# alu_schem_1.net
KiCad netlist of a schematic drawn in Altium Designer
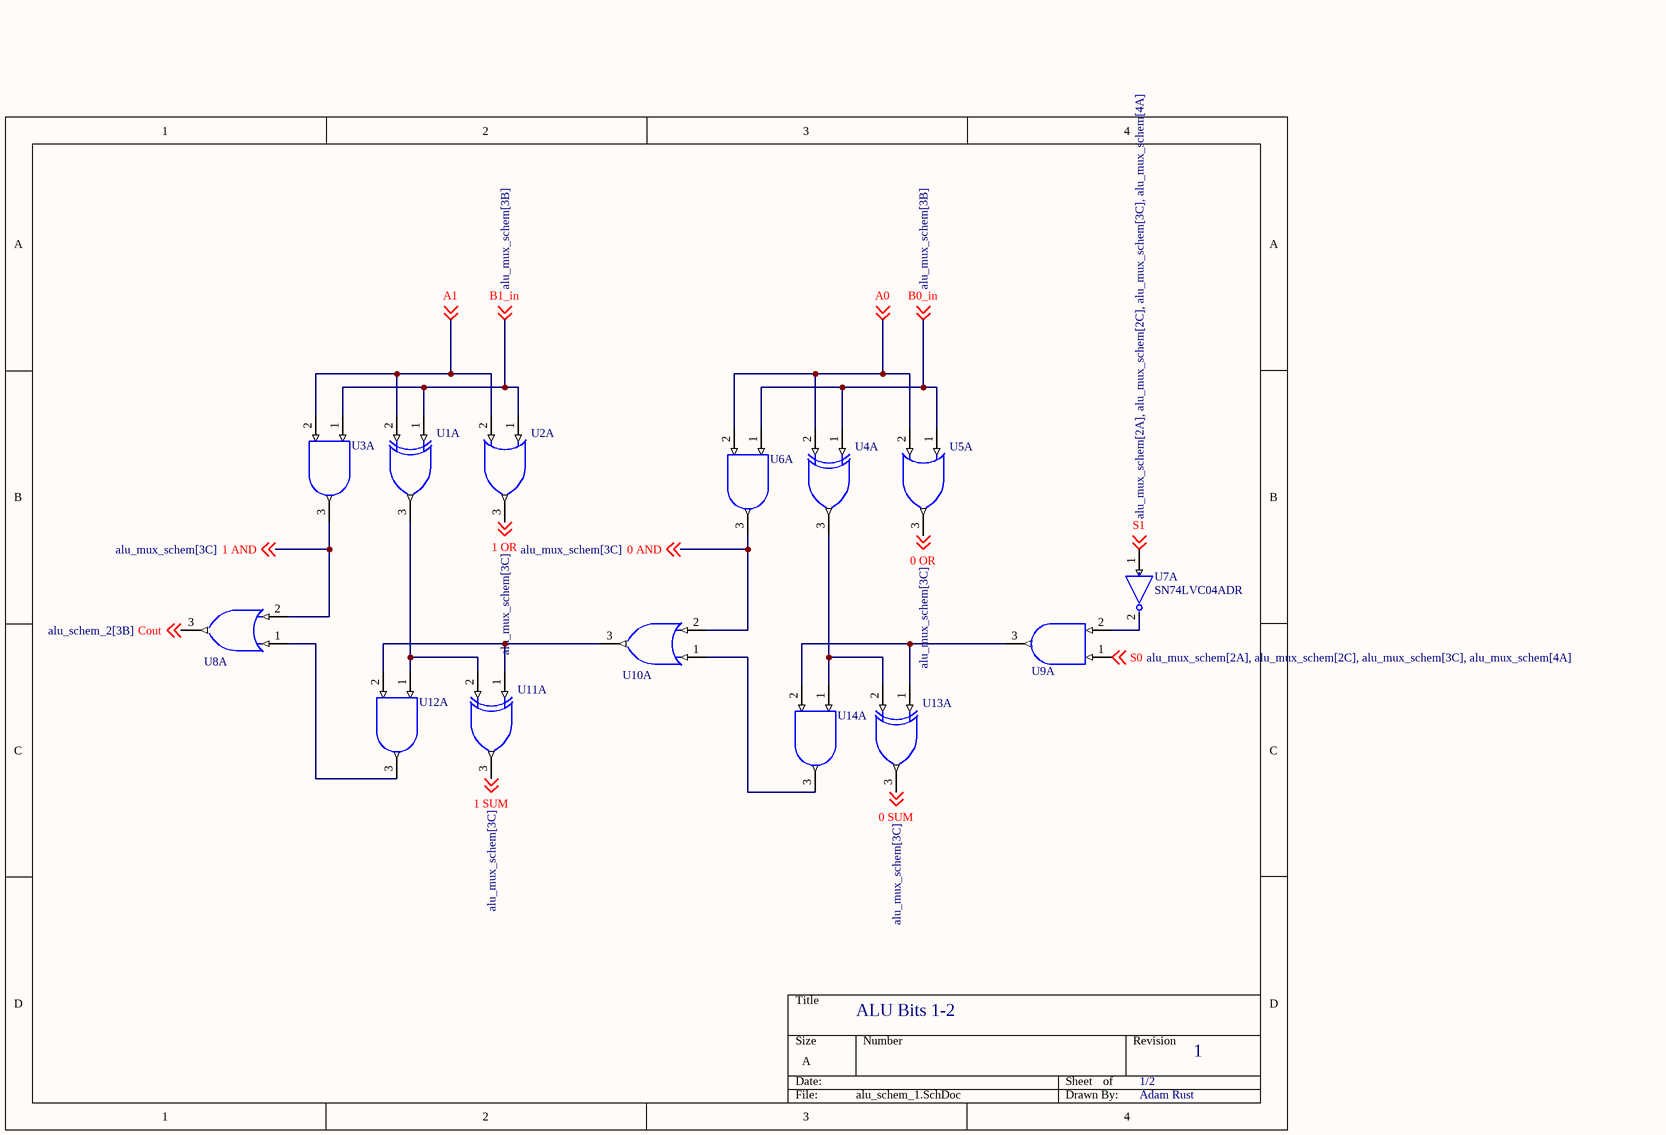
[diagram p0: alu_schem_1.SchDoc]

(export (version "E")
  (design (tool "Eeschema 10.0.6"))
  (components
    (comp (ref "U1")
      (value "SN74LVC86ARGYR")
      (footprint "RGY0014A_V")
      (description "Quadruple 2-Input Exclusive-OR Gate, RGY0014A, LARGE T&R")
      (fields
        (field (name "GENERIC PART NUMBER") "SN74LVC86A")
        (field (name "MANUFACTURER") "Texas Instruments")
      )
      (libsource (lib "Altium Content Vault") (part "TI-XOR-4-2IN-RGY0014A-14"))
    )
    (comp (ref "U2")
      (value "SN74LVC32APWRG4")
      (footprint "PW0014A_N")
      (description "Quadruple 2-Input Positive-OR Gate, PW0014A, LARGE T&R")
      (fields
        (field (name "GENERIC PART NUMBER") "SN74LVC32A")
        (field (name "MANUFACTURER") "Texas Instruments")
      )
      (libsource (lib "Altium Content Vault") (part "TI-OR-4-2IN-14"))
    )
    (comp (ref "U3")
      (value "SN74LVC08ADR")
      (footprint "D0014A_N")
      (description "Quadruple 2-Input Positive-AND Gate, D0014A, LARGE T&R")
      (fields
        (field (name "MANUFACTURER") "Texas Instruments")
        (field (name "GENERIC PART NUMBER") "SN74LVC08A")
      )
      (libsource (lib "Altium Content Vault") (part "TI-AND-4-2IN-14"))
    )
    (comp (ref "U4")
      (value "SN74LVC86ARGYR")
      (footprint "RGY0014A_V")
      (description "Quadruple 2-Input Exclusive-OR Gate, RGY0014A, LARGE T&R")
      (fields
        (field (name "GENERIC PART NUMBER") "SN74LVC86A")
        (field (name "MANUFACTURER") "Texas Instruments")
      )
      (libsource (lib "Altium Content Vault") (part "TI-XOR-4-2IN-RGY0014A-14"))
    )
    (comp (ref "U5")
      (value "SN74LVC32APWRG4")
      (footprint "PW0014A_N")
      (description "Quadruple 2-Input Positive-OR Gate, PW0014A, LARGE T&R")
      (fields
        (field (name "GENERIC PART NUMBER") "SN74LVC32A")
        (field (name "MANUFACTURER") "Texas Instruments")
      )
      (libsource (lib "Altium Content Vault") (part "TI-OR-4-2IN-14"))
    )
    (comp (ref "U6")
      (value "SN74LVC08ADR")
      (footprint "D0014A_N")
      (description "Quadruple 2-Input Positive-AND Gate, D0014A, LARGE T&R")
      (fields
        (field (name "MANUFACTURER") "Texas Instruments")
        (field (name "GENERIC PART NUMBER") "SN74LVC08A")
      )
      (libsource (lib "Altium Content Vault") (part "TI-AND-4-2IN-14"))
    )
    (comp (ref "U7")
      (value "SN74LVC04ADR")
      (footprint "FP-D0014A-IPC_A")
      (description "IC INVERTER 6CH 6-INP 14SOIC")
      (libsource (lib "Altium Content Vault") (part "709a8d2d34fac73d54705890335673b"))
    )
    (comp (ref "U8")
      (value "SN74LVC32APWRG4")
      (footprint "PW0014A_N")
      (description "Quadruple 2-Input Positive-OR Gate, PW0014A, LARGE T&R")
      (fields
        (field (name "GENERIC PART NUMBER") "SN74LVC32A")
        (field (name "MANUFACTURER") "Texas Instruments")
      )
      (libsource (lib "") (part "TI-OR-4-2IN-14_1"))
    )
    (comp (ref "U9")
      (value "SN74LVC08ADR")
      (footprint "D0014A_N")
      (description "Quadruple 2-Input Positive-AND Gate, D0014A, LARGE T&R")
      (fields
        (field (name "MANUFACTURER") "Texas Instruments")
        (field (name "GENERIC PART NUMBER") "SN74LVC08A")
      )
      (libsource (lib "") (part "TI-AND-4-2IN-14_1"))
    )
    (comp (ref "U10")
      (value "SN74LVC32APWRG4")
      (footprint "PW0014A_N")
      (description "Quadruple 2-Input Positive-OR Gate, PW0014A, LARGE T&R")
      (fields
        (field (name "GENERIC PART NUMBER") "SN74LVC32A")
        (field (name "MANUFACTURER") "Texas Instruments")
      )
      (libsource (lib "") (part "TI-OR-4-2IN-14_1"))
    )
    (comp (ref "U11")
      (value "SN74LVC86ARGYR")
      (footprint "RGY0014A_V")
      (description "Quadruple 2-Input Exclusive-OR Gate, RGY0014A, LARGE T&R")
      (fields
        (field (name "GENERIC PART NUMBER") "SN74LVC86A")
        (field (name "MANUFACTURER") "Texas Instruments")
      )
      (libsource (lib "Altium Content Vault") (part "TI-XOR-4-2IN-RGY0014A-14"))
    )
    (comp (ref "U12")
      (value "SN74LVC08ADR")
      (footprint "D0014A_N")
      (description "Quadruple 2-Input Positive-AND Gate, D0014A, LARGE T&R")
      (fields
        (field (name "MANUFACTURER") "Texas Instruments")
        (field (name "GENERIC PART NUMBER") "SN74LVC08A")
      )
      (libsource (lib "Altium Content Vault") (part "TI-AND-4-2IN-14"))
    )
    (comp (ref "U13")
      (value "SN74LVC86ARGYR")
      (footprint "RGY0014A_V")
      (description "Quadruple 2-Input Exclusive-OR Gate, RGY0014A, LARGE T&R")
      (fields
        (field (name "GENERIC PART NUMBER") "SN74LVC86A")
        (field (name "MANUFACTURER") "Texas Instruments")
      )
      (libsource (lib "Altium Content Vault") (part "TI-XOR-4-2IN-RGY0014A-14"))
    )
    (comp (ref "U14")
      (value "SN74LVC08ADR")
      (footprint "D0014A_N")
      (description "Quadruple 2-Input Positive-AND Gate, D0014A, LARGE T&R")
      (fields
        (field (name "MANUFACTURER") "Texas Instruments")
        (field (name "GENERIC PART NUMBER") "SN74LVC08A")
      )
      (libsource (lib "Altium Content Vault") (part "TI-AND-4-2IN-14"))
    )
  )
  (nets
    (net (code "1") (name "0 AND") (class "Default")
      (node (ref "U10") (pin "2") (pinfunction "1B_2") (pintype "input"))
      (node (ref "U6") (pin "3") (pinfunction "1Y_3") (pintype "output"))
    )
    (net (code "2") (name "0 OR") (class "Default")
      (node (ref "U5") (pin "3") (pinfunction "1Y_3") (pintype "output"))
    )
    (net (code "3") (name "0 SUM") (class "Default")
      (node (ref "U13") (pin "3") (pinfunction "1Y_3") (pintype "output"))
    )
    (net (code "4") (name "1 AND") (class "Default")
      (node (ref "U3") (pin "3") (pinfunction "1Y_3") (pintype "output"))
      (node (ref "U8") (pin "2") (pinfunction "1B_2") (pintype "input"))
    )
    (net (code "5") (name "1 OR") (class "Default")
      (node (ref "U2") (pin "3") (pinfunction "1Y_3") (pintype "output"))
    )
    (net (code "6") (name "1 SUM") (class "Default")
      (node (ref "U11") (pin "3") (pinfunction "1Y_3") (pintype "output"))
    )
    (net (code "7") (name "A0") (class "Default")
      (node (ref "U4") (pin "2") (pinfunction "1B_2") (pintype "input"))
      (node (ref "U5") (pin "2") (pinfunction "1B_2") (pintype "input"))
      (node (ref "U6") (pin "2") (pinfunction "1B_2") (pintype "input"))
    )
    (net (code "8") (name "A1") (class "Default")
      (node (ref "U1") (pin "2") (pinfunction "1B_2") (pintype "input"))
      (node (ref "U2") (pin "2") (pinfunction "1B_2") (pintype "input"))
      (node (ref "U3") (pin "2") (pinfunction "1B_2") (pintype "input"))
    )
    (net (code "9") (name "B0_in") (class "Default")
      (node (ref "U4") (pin "1") (pinfunction "1A_1") (pintype "input"))
      (node (ref "U5") (pin "1") (pinfunction "1A_1") (pintype "input"))
      (node (ref "U6") (pin "1") (pinfunction "1A_1") (pintype "input"))
    )
    (net (code "10") (name "B1_in") (class "Default")
      (node (ref "U1") (pin "1") (pinfunction "1A_1") (pintype "input"))
      (node (ref "U2") (pin "1") (pinfunction "1A_1") (pintype "input"))
      (node (ref "U3") (pin "1") (pinfunction "1A_1") (pintype "input"))
    )
    (net (code "11") (name "Cout") (class "Default")
      (node (ref "U8") (pin "3") (pinfunction "1Y_3") (pintype "output"))
    )
    (net (code "12") (name "Net-(U7A-1Y)") (class "Default")
      (node (ref "U7") (pin "2") (pinfunction "1Y_2") (pintype "output"))
      (node (ref "U9") (pin "2") (pinfunction "1B_2") (pintype "input"))
    )
    (net (code "13") (name "Net-(U10A-1A)") (class "Default")
      (node (ref "U10") (pin "1") (pinfunction "1A_1") (pintype "input"))
      (node (ref "U14") (pin "3") (pinfunction "1Y_3") (pintype "output"))
    )
    (net (code "14") (name "Net-(U10A-1Y)") (class "Default")
      (node (ref "U10") (pin "3") (pinfunction "1Y_3") (pintype "output"))
      (node (ref "U11") (pin "1") (pinfunction "1A_1") (pintype "input"))
      (node (ref "U12") (pin "2") (pinfunction "1B_2") (pintype "input"))
    )
    (net (code "15") (name "Net-(U11A-1B)") (class "Default")
      (node (ref "U1") (pin "3") (pinfunction "1Y_3") (pintype "output"))
      (node (ref "U11") (pin "2") (pinfunction "1B_2") (pintype "input"))
      (node (ref "U12") (pin "1") (pinfunction "1A_1") (pintype "input"))
    )
    (net (code "16") (name "Net-(U12A-1Y)") (class "Default")
      (node (ref "U12") (pin "3") (pinfunction "1Y_3") (pintype "output"))
      (node (ref "U8") (pin "1") (pinfunction "1A_1") (pintype "input"))
    )
    (net (code "17") (name "Net-(U13A-1A)") (class "Default")
      (node (ref "U13") (pin "1") (pinfunction "1A_1") (pintype "input"))
      (node (ref "U14") (pin "2") (pinfunction "1B_2") (pintype "input"))
      (node (ref "U9") (pin "3") (pinfunction "1Y_3") (pintype "output"))
    )
    (net (code "18") (name "Net-(U13A-1B)") (class "Default")
      (node (ref "U13") (pin "2") (pinfunction "1B_2") (pintype "input"))
      (node (ref "U14") (pin "1") (pinfunction "1A_1") (pintype "input"))
      (node (ref "U4") (pin "3") (pinfunction "1Y_3") (pintype "output"))
    )
    (net (code "19") (name "S0") (class "Default")
      (node (ref "U9") (pin "1") (pinfunction "1A_1") (pintype "input"))
    )
    (net (code "20") (name "S1") (class "Default")
      (node (ref "U7") (pin "1") (pinfunction "1A_1") (pintype "input"))
    )
  )
)
